# Master-MCU.net
KiCad netlist of a schematic drawn in Altium Designer
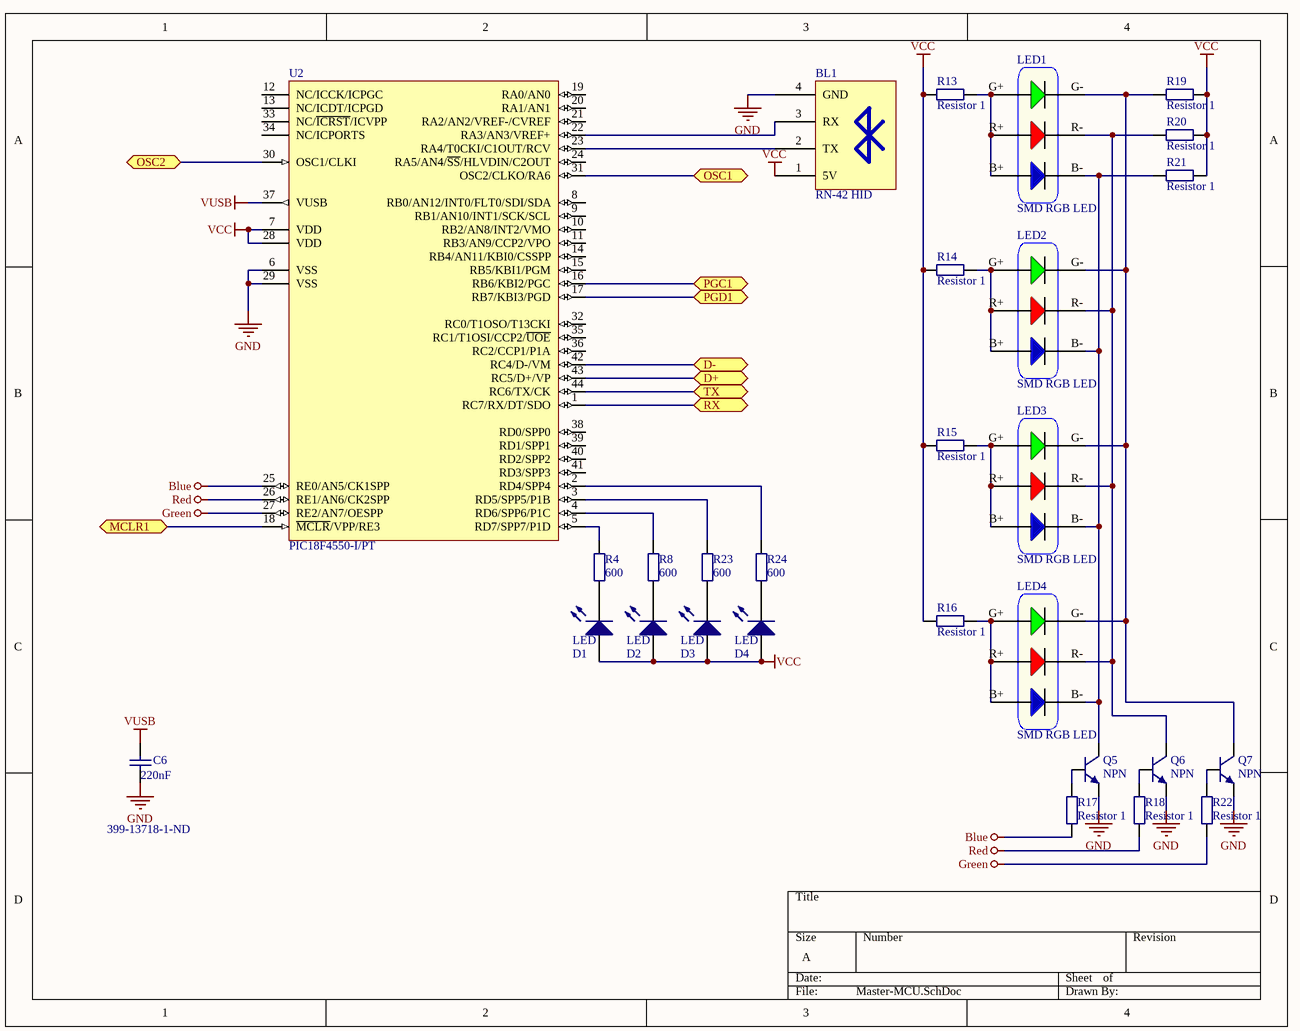
[diagram p0: Master-MCU.SchDoc]

(export (version "E")
  (design (tool "Eeschema 10.0.6"))
  (components
    (comp (ref "BL1")
      (value "RN-42 HID")
      (footprint "Bluetooth module for PCB mounting")
      (libsource (lib "RN42 Breakout SCH Library") (part "Bluetooth module for PCB mounting"))
    )
    (comp (ref "C6")
      (value "220nF")
      (footprint "C-0603")
      (description "Capacitor")
      (fields (field (name "SUPPLIER PART NUMBER 1") "399-13718-1-ND"))
      (libsource (lib "Max Library") (part "Capacitor 1"))
    )
    (comp (ref "D1")
      (value "LED")
      (footprint "JV Footprints:LED-SMD-R")
      (description "Typical LED")
      (fields (field (name "PUBLISHER") "Altium Limited"))
      (libsource (lib "Max Library") (part "LED"))
    )
    (comp (ref "D2")
      (value "LED")
      (footprint "JV Footprints:LED-SMD-R")
      (description "Typical LED")
      (fields (field (name "PUBLISHER") "Altium Limited"))
      (libsource (lib "Max Library") (part "LED"))
    )
    (comp (ref "D3")
      (value "LED")
      (footprint "LED-SMD-R")
      (description "Typical LED")
      (fields (field (name "PUBLISHER") "Altium Limited"))
      (libsource (lib "Max Library") (part "LED"))
    )
    (comp (ref "D4")
      (value "LED")
      (footprint "LED-SMD-R")
      (description "Typical LED")
      (fields (field (name "PUBLISHER") "Altium Limited"))
      (libsource (lib "Max Library") (part "LED"))
    )
    (comp (ref "LED1")
      (value "SMD RGB LED")
      (footprint "SMD LED")
      (description "https://www.tweaking4all.com/wp-content/uploads/2014/01/5050LED.pdf")
      (libsource (lib "LED SYMBOL") (part "LED"))
    )
    (comp (ref "LED2")
      (value "SMD RGB LED")
      (footprint "SMD LED")
      (description "https://www.tweaking4all.com/wp-content/uploads/2014/01/5050LED.pdf")
      (libsource (lib "LED SYMBOL") (part "LED"))
    )
    (comp (ref "LED3")
      (value "SMD RGB LED")
      (footprint "SMD LED")
      (description "https://www.tweaking4all.com/wp-content/uploads/2014/01/5050LED.pdf")
      (libsource (lib "LED SYMBOL") (part "LED"))
    )
    (comp (ref "LED4")
      (value "SMD RGB LED")
      (footprint "SMD LED")
      (description "https://www.tweaking4all.com/wp-content/uploads/2014/01/5050LED.pdf")
      (libsource (lib "LED SYMBOL") (part "LED"))
    )
    (comp (ref "Q5")
      (value "NPN")
      (footprint "JV Footprints:SOT95P237X111-3M-JV")
      (description "NPN General Purpose Amplifier")
      (fields (field (name "PUBLISHER") "Altium Limited"))
      (libsource (lib "Max Library") (part "Transistor NPN"))
    )
    (comp (ref "Q6")
      (value "NPN")
      (footprint "JV Footprints:SOT95P237X111-3M-JV")
      (description "NPN General Purpose Amplifier")
      (fields (field (name "PUBLISHER") "Altium Limited"))
      (libsource (lib "Max Library") (part "Transistor NPN"))
    )
    (comp (ref "Q7")
      (value "NPN")
      (footprint "JV Footprints:SOT95P237X111-3M-JV")
      (description "NPN General Purpose Amplifier")
      (fields (field (name "PUBLISHER") "Altium Limited"))
      (libsource (lib "Max Library") (part "Transistor NPN"))
    )
    (comp (ref "R4")
      (value "600")
      (footprint "JV Footprints:R-0603-3D")
      (description "Resistor")
      (libsource (lib "Max Library") (part "Resistor 1"))
    )
    (comp (ref "R8")
      (value "600")
      (footprint "JV Footprints:R-0603-3D")
      (description "Resistor")
      (libsource (lib "Max Library") (part "Resistor 1"))
    )
    (comp (ref "R13")
      (value "Resistor 1")
      (footprint "JV Footprints:R-0603-3D")
      (description "Resistor")
      (libsource (lib "") (part "Resistor 1_2"))
    )
    (comp (ref "R14")
      (value "Resistor 1")
      (footprint "JV Footprints:R-0603-3D")
      (description "Resistor")
      (libsource (lib "") (part "Resistor 1_2"))
    )
    (comp (ref "R15")
      (value "Resistor 1")
      (footprint "JV Footprints:R-0603-3D")
      (description "Resistor")
      (libsource (lib "") (part "Resistor 1_2"))
    )
    (comp (ref "R16")
      (value "Resistor 1")
      (footprint "JV Footprints:R-0603-3D")
      (description "Resistor")
      (libsource (lib "") (part "Resistor 1_2"))
    )
    (comp (ref "R17")
      (value "Resistor 1")
      (footprint "JV Footprints:R-0603-3D")
      (description "Resistor")
      (libsource (lib "") (part "Resistor 1_3"))
    )
    (comp (ref "R18")
      (value "Resistor 1")
      (footprint "JV Footprints:R-0603-3D")
      (description "Resistor")
      (libsource (lib "") (part "Resistor 1_3"))
    )
    (comp (ref "R19")
      (value "Resistor 1")
      (footprint "R-0603-3D")
      (description "Resistor")
      (libsource (lib "") (part "Resistor 1_1"))
    )
    (comp (ref "R20")
      (value "Resistor 1")
      (footprint "JV Footprints:R-0603-3D")
      (description "Resistor")
      (libsource (lib "") (part "Resistor 1_1"))
    )
    (comp (ref "R21")
      (value "Resistor 1")
      (footprint "JV Footprints:R-0603-3D")
      (description "Resistor")
      (libsource (lib "") (part "Resistor 1_1"))
    )
    (comp (ref "R22")
      (value "Resistor 1")
      (footprint "JV Footprints:R-0603-3D")
      (description "Resistor")
      (libsource (lib "") (part "Resistor 1_3"))
    )
    (comp (ref "R23")
      (value "600")
      (footprint "JV Footprints:R-0603-3D")
      (description "Resistor")
      (libsource (lib "Max Library") (part "Resistor 1"))
    )
    (comp (ref "R24")
      (value "600")
      (footprint "JV Footprints:R-0603-3D")
      (description "Resistor")
      (libsource (lib "Max Library") (part "Resistor 1"))
    )
    (comp (ref "U2")
      (value "PIC18F4550-I/PT")
      (footprint "JV Footprints:TQFP-44_JV")
      (fields (field (name "PUBLISHER") "Altium Limited"))
      (libsource (lib "Microchip Microcontroller 8-Bit PIC18") (part "PIC18F4550-I/PT"))
    )
  )
  (nets
    (net (code "1") (name "/D+") (class "Default")
      (node (ref "U2") (pin "43") (pinfunction "RC5/D+/VP_43") (pintype "bidirectional"))
    )
    (net (code "2") (name "/D-") (class "Default")
      (node (ref "U2") (pin "42") (pinfunction "RC4/D-/VM_42") (pintype "bidirectional"))
    )
    (net (code "3") (name "/MCLR1") (class "Default")
      (node (ref "U2") (pin "18") (pinfunction "~{MCLR}/VPP/RE3_18") (pintype "input"))
    )
    (net (code "4") (name "/OSC1") (class "Default")
      (node (ref "U2") (pin "31") (pinfunction "OSC2/CLKO/RA6_31") (pintype "bidirectional"))
    )
    (net (code "5") (name "/OSC2") (class "Default")
      (node (ref "U2") (pin "30") (pinfunction "OSC1/CLKI_30") (pintype "input"))
    )
    (net (code "6") (name "/PGC1") (class "Default")
      (node (ref "U2") (pin "16") (pinfunction "RB6/KBI2/PGC_16") (pintype "bidirectional"))
    )
    (net (code "7") (name "/PGD1") (class "Default")
      (node (ref "U2") (pin "17") (pinfunction "RB7/KBI3/PGD_17") (pintype "bidirectional"))
    )
    (net (code "8") (name "/RX") (class "Default")
      (node (ref "U2") (pin "1") (pinfunction "RC7/RX/DT/SDO_1") (pintype "bidirectional"))
    )
    (net (code "9") (name "/TX") (class "Default")
      (node (ref "U2") (pin "44") (pinfunction "RC6/TX/CK_44") (pintype "bidirectional"))
    )
    (net (code "10") (name "Blue") (class "Default")
      (node (ref "R17") (pin "1") (pinfunction "1_1") (pintype "passive"))
      (node (ref "U2") (pin "25") (pinfunction "RE0/AN5/CK1SPP_25") (pintype "bidirectional"))
    )
    (net (code "11") (name "GND") (class "Default")
      (node (ref "BL1") (pin "4") (pinfunction "GND_4") (pintype "power_in"))
      (node (ref "C6") (pin "1") (pinfunction "1_1") (pintype "passive"))
      (node (ref "Q5") (pin "1") (pinfunction "E_1") (pintype "passive"))
      (node (ref "Q6") (pin "1") (pinfunction "E_1") (pintype "passive"))
      (node (ref "Q7") (pin "1") (pinfunction "E_1") (pintype "passive"))
      (node (ref "U2") (pin "29") (pinfunction "VSS_29") (pintype "power_in"))
      (node (ref "U2") (pin "6") (pinfunction "VSS_6") (pintype "power_in"))
    )
    (net (code "12") (name "Green") (class "Default")
      (node (ref "R22") (pin "1") (pinfunction "1_1") (pintype "passive"))
      (node (ref "U2") (pin "27") (pinfunction "RE2/AN7/OESPP_27") (pintype "bidirectional"))
    )
    (net (code "13") (name "Net-(BL1-RX)") (class "Default")
      (node (ref "BL1") (pin "3") (pinfunction "RX_3") (pintype "passive"))
      (node (ref "U2") (pin "22") (pinfunction "RA3/AN3/VREF+_22") (pintype "bidirectional"))
    )
    (net (code "14") (name "Net-(BL1-TX)") (class "Default")
      (node (ref "BL1") (pin "2") (pinfunction "TX_2") (pintype "passive"))
      (node (ref "U2") (pin "23") (pinfunction "RA4/T0CKI/C1OUT/RCV_23") (pintype "bidirectional"))
    )
    (net (code "15") (name "Net-(D1-K)") (class "Default")
      (node (ref "D1") (pin "2") (pinfunction "K_2") (pintype "passive"))
      (node (ref "R4") (pin "2") (pinfunction "2_2") (pintype "passive"))
    )
    (net (code "16") (name "Net-(D2-K)") (class "Default")
      (node (ref "D2") (pin "2") (pinfunction "K_2") (pintype "passive"))
      (node (ref "R8") (pin "2") (pinfunction "2_2") (pintype "passive"))
    )
    (net (code "17") (name "Net-(D3-K)") (class "Default")
      (node (ref "D3") (pin "2") (pinfunction "K_2") (pintype "passive"))
      (node (ref "R23") (pin "2") (pinfunction "2_2") (pintype "passive"))
    )
    (net (code "18") (name "Net-(D4-K)") (class "Default")
      (node (ref "D4") (pin "2") (pinfunction "K_2") (pintype "passive"))
      (node (ref "R24") (pin "2") (pinfunction "2_2") (pintype "passive"))
    )
    (net (code "19") (name "Net-(LED1-PadB+)") (class "Default")
      (node (ref "LED1") (pin "B+") (pinfunction "B+_B+") (pintype "passive"))
      (node (ref "LED1") (pin "G+") (pinfunction "G+_G+") (pintype "passive"))
      (node (ref "LED1") (pin "R+") (pinfunction "R+_R+") (pintype "passive"))
      (node (ref "R13") (pin "2") (pinfunction "2_2") (pintype "passive"))
    )
    (net (code "20") (name "Net-(LED2-PadB+)") (class "Default")
      (node (ref "LED2") (pin "B+") (pinfunction "B+_B+") (pintype "passive"))
      (node (ref "LED2") (pin "G+") (pinfunction "G+_G+") (pintype "passive"))
      (node (ref "LED2") (pin "R+") (pinfunction "R+_R+") (pintype "passive"))
      (node (ref "R14") (pin "2") (pinfunction "2_2") (pintype "passive"))
    )
    (net (code "21") (name "Net-(LED3-PadB+)") (class "Default")
      (node (ref "LED3") (pin "B+") (pinfunction "B+_B+") (pintype "passive"))
      (node (ref "LED3") (pin "G+") (pinfunction "G+_G+") (pintype "passive"))
      (node (ref "LED3") (pin "R+") (pinfunction "R+_R+") (pintype "passive"))
      (node (ref "R15") (pin "2") (pinfunction "2_2") (pintype "passive"))
    )
    (net (code "22") (name "Net-(LED4-PadB+)") (class "Default")
      (node (ref "LED4") (pin "B+") (pinfunction "B+_B+") (pintype "passive"))
      (node (ref "LED4") (pin "G+") (pinfunction "G+_G+") (pintype "passive"))
      (node (ref "LED4") (pin "R+") (pinfunction "R+_R+") (pintype "passive"))
      (node (ref "R16") (pin "2") (pinfunction "2_2") (pintype "passive"))
    )
    (net (code "23") (name "Net-(Q5-B)") (class "Default")
      (node (ref "Q5") (pin "2") (pinfunction "B_2") (pintype "passive"))
      (node (ref "R17") (pin "2") (pinfunction "2_2") (pintype "passive"))
    )
    (net (code "24") (name "Net-(Q5-C)") (class "Default")
      (node (ref "LED1") (pin "B-") (pinfunction "B-_B-") (pintype "passive"))
      (node (ref "LED2") (pin "B-") (pinfunction "B-_B-") (pintype "passive"))
      (node (ref "LED3") (pin "B-") (pinfunction "B-_B-") (pintype "passive"))
      (node (ref "LED4") (pin "B-") (pinfunction "B-_B-") (pintype "passive"))
      (node (ref "Q5") (pin "3") (pinfunction "C_3") (pintype "passive"))
      (node (ref "R21") (pin "2") (pinfunction "2_2") (pintype "passive"))
    )
    (net (code "25") (name "Net-(Q6-B)") (class "Default")
      (node (ref "Q6") (pin "2") (pinfunction "B_2") (pintype "passive"))
      (node (ref "R18") (pin "2") (pinfunction "2_2") (pintype "passive"))
    )
    (net (code "26") (name "Net-(Q6-C)") (class "Default")
      (node (ref "LED1") (pin "R-") (pinfunction "R-_R-") (pintype "passive"))
      (node (ref "LED2") (pin "R-") (pinfunction "R-_R-") (pintype "passive"))
      (node (ref "LED3") (pin "R-") (pinfunction "R-_R-") (pintype "passive"))
      (node (ref "LED4") (pin "R-") (pinfunction "R-_R-") (pintype "passive"))
      (node (ref "Q6") (pin "3") (pinfunction "C_3") (pintype "passive"))
      (node (ref "R20") (pin "2") (pinfunction "2_2") (pintype "passive"))
    )
    (net (code "27") (name "Net-(Q7-B)") (class "Default")
      (node (ref "Q7") (pin "2") (pinfunction "B_2") (pintype "passive"))
      (node (ref "R22") (pin "2") (pinfunction "2_2") (pintype "passive"))
    )
    (net (code "28") (name "Net-(Q7-C)") (class "Default")
      (node (ref "LED1") (pin "G-") (pinfunction "G-_G-") (pintype "passive"))
      (node (ref "LED2") (pin "G-") (pinfunction "G-_G-") (pintype "passive"))
      (node (ref "LED3") (pin "G-") (pinfunction "G-_G-") (pintype "passive"))
      (node (ref "LED4") (pin "G-") (pinfunction "G-_G-") (pintype "passive"))
      (node (ref "Q7") (pin "3") (pinfunction "C_3") (pintype "passive"))
      (node (ref "R19") (pin "2") (pinfunction "2_2") (pintype "passive"))
    )
    (net (code "29") (name "Net-(U2-RD4{slash}SPP4)") (class "Default")
      (node (ref "R24") (pin "1") (pinfunction "1_1") (pintype "passive"))
      (node (ref "U2") (pin "2") (pinfunction "RD4/SPP4_2") (pintype "bidirectional"))
    )
    (net (code "30") (name "Net-(U2-RD5{slash}SPP5{slash}P1B)") (class "Default")
      (node (ref "R23") (pin "1") (pinfunction "1_1") (pintype "passive"))
      (node (ref "U2") (pin "3") (pinfunction "RD5/SPP5/P1B_3") (pintype "bidirectional"))
    )
    (net (code "31") (name "Net-(U2-RD6{slash}SPP6{slash}P1C)") (class "Default")
      (node (ref "R8") (pin "1") (pinfunction "1_1") (pintype "passive"))
      (node (ref "U2") (pin "4") (pinfunction "RD6/SPP6/P1C_4") (pintype "bidirectional"))
    )
    (net (code "32") (name "Net-(U2-RD7{slash}SPP7{slash}P1D)") (class "Default")
      (node (ref "R4") (pin "1") (pinfunction "1_1") (pintype "passive"))
      (node (ref "U2") (pin "5") (pinfunction "RD7/SPP7/P1D_5") (pintype "bidirectional"))
    )
    (net (code "33") (name "Red") (class "Default")
      (node (ref "R18") (pin "1") (pinfunction "1_1") (pintype "passive"))
      (node (ref "U2") (pin "26") (pinfunction "RE1/AN6/CK2SPP_26") (pintype "bidirectional"))
    )
    (net (code "34") (name "VCC") (class "Default")
      (node (ref "BL1") (pin "1") (pinfunction "5V_1") (pintype "power_in"))
      (node (ref "D1") (pin "1") (pinfunction "A_1") (pintype "passive"))
      (node (ref "D2") (pin "1") (pinfunction "A_1") (pintype "passive"))
      (node (ref "D3") (pin "1") (pinfunction "A_1") (pintype "passive"))
      (node (ref "D4") (pin "1") (pinfunction "A_1") (pintype "passive"))
      (node (ref "R13") (pin "1") (pinfunction "1_1") (pintype "passive"))
      (node (ref "R14") (pin "1") (pinfunction "1_1") (pintype "passive"))
      (node (ref "R15") (pin "1") (pinfunction "1_1") (pintype "passive"))
      (node (ref "R16") (pin "1") (pinfunction "1_1") (pintype "passive"))
      (node (ref "R19") (pin "1") (pinfunction "1_1") (pintype "passive"))
      (node (ref "R20") (pin "1") (pinfunction "1_1") (pintype "passive"))
      (node (ref "R21") (pin "1") (pinfunction "1_1") (pintype "passive"))
      (node (ref "U2") (pin "28") (pinfunction "VDD_28") (pintype "power_in"))
      (node (ref "U2") (pin "7") (pinfunction "VDD_7") (pintype "power_in"))
    )
    (net (code "35") (name "VUSB") (class "Default")
      (node (ref "C6") (pin "2") (pinfunction "2_2") (pintype "passive"))
      (node (ref "U2") (pin "37") (pinfunction "VUSB_37") (pintype "output"))
    )
    (net (code "36") (name "unconnected-(U2-NC{slash}ICCK{slash}ICPGC-Pad12)") (class "Default")
      (node (ref "U2") (pin "12") (pinfunction "NC/ICCK/ICPGC_12") (pintype "passive"))
    )
    (net (code "37") (name "unconnected-(U2-NC{slash}ICDT{slash}ICPGD-Pad13)") (class "Default")
      (node (ref "U2") (pin "13") (pinfunction "NC/ICDT/ICPGD_13") (pintype "passive"))
    )
    (net (code "38") (name "unconnected-(U2-NC{slash}ICPORTS-Pad34)") (class "Default")
      (node (ref "U2") (pin "34") (pinfunction "NC/ICPORTS_34") (pintype "passive"))
    )
    (net (code "39") (name "unconnected-(U2-NC{slash}~{ICRST}{slash}ICVPP-Pad33)") (class "Default")
      (node (ref "U2") (pin "33") (pinfunction "NC/~{ICRST}/ICVPP_33") (pintype "passive"))
    )
    (net (code "40") (name "unconnected-(U2-RA0{slash}AN0-Pad19)") (class "Default")
      (node (ref "U2") (pin "19") (pinfunction "RA0/AN0_19") (pintype "bidirectional"))
    )
    (net (code "41") (name "unconnected-(U2-RA1{slash}AN1-Pad20)") (class "Default")
      (node (ref "U2") (pin "20") (pinfunction "RA1/AN1_20") (pintype "bidirectional"))
    )
    (net (code "42") (name "unconnected-(U2-RA2{slash}AN2{slash}VREF-{slash}CVREF-Pad21)") (class "Default")
      (node (ref "U2") (pin "21") (pinfunction "RA2/AN2/VREF-/CVREF_21") (pintype "bidirectional"))
    )
    (net (code "43") (name "unconnected-(U2-RA5{slash}AN4{slash}~{SS}{slash}HLVDIN{slash}C2OUT-Pad24)") (class "Default")
      (node (ref "U2") (pin "24") (pinfunction "RA5/AN4/~{SS}/HLVDIN/C2OUT_24") (pintype "bidirectional"))
    )
    (net (code "44") (name "unconnected-(U2-RB0{slash}AN12{slash}INT0{slash}FLT0{slash}SDI{slash}SDA-Pad8)") (class "Default")
      (node (ref "U2") (pin "8") (pinfunction "RB0/AN12/INT0/FLT0/SDI/SDA_8") (pintype "bidirectional"))
    )
    (net (code "45") (name "unconnected-(U2-RB1{slash}AN10{slash}INT1{slash}SCK{slash}SCL-Pad9)") (class "Default")
      (node (ref "U2") (pin "9") (pinfunction "RB1/AN10/INT1/SCK/SCL_9") (pintype "bidirectional"))
    )
    (net (code "46") (name "unconnected-(U2-RB2{slash}AN8{slash}INT2{slash}VMO-Pad10)") (class "Default")
      (node (ref "U2") (pin "10") (pinfunction "RB2/AN8/INT2/VMO_10") (pintype "bidirectional"))
    )
    (net (code "47") (name "unconnected-(U2-RB3{slash}AN9{slash}CCP2{slash}VPO-Pad11)") (class "Default")
      (node (ref "U2") (pin "11") (pinfunction "RB3/AN9/CCP2/VPO_11") (pintype "bidirectional"))
    )
    (net (code "48") (name "unconnected-(U2-RB4{slash}AN11{slash}KBI0{slash}CSSPP-Pad14)") (class "Default")
      (node (ref "U2") (pin "14") (pinfunction "RB4/AN11/KBI0/CSSPP_14") (pintype "bidirectional"))
    )
    (net (code "49") (name "unconnected-(U2-RB5{slash}KBI1{slash}PGM-Pad15)") (class "Default")
      (node (ref "U2") (pin "15") (pinfunction "RB5/KBI1/PGM_15") (pintype "bidirectional"))
    )
    (net (code "50") (name "unconnected-(U2-RC0{slash}T1OSO{slash}T13CKI-Pad32)") (class "Default")
      (node (ref "U2") (pin "32") (pinfunction "RC0/T1OSO/T13CKI_32") (pintype "bidirectional"))
    )
    (net (code "51") (name "unconnected-(U2-RC1{slash}T1OSI{slash}CCP2{slash}~{UOE}-Pad35)") (class "Default")
      (node (ref "U2") (pin "35") (pinfunction "RC1/T1OSI/CCP2/~{UOE}_35") (pintype "bidirectional"))
    )
    (net (code "52") (name "unconnected-(U2-RC2{slash}CCP1{slash}P1A-Pad36)") (class "Default")
      (node (ref "U2") (pin "36") (pinfunction "RC2/CCP1/P1A_36") (pintype "bidirectional"))
    )
    (net (code "53") (name "unconnected-(U2-RD0{slash}SPP0-Pad38)") (class "Default")
      (node (ref "U2") (pin "38") (pinfunction "RD0/SPP0_38") (pintype "bidirectional"))
    )
    (net (code "54") (name "unconnected-(U2-RD1{slash}SPP1-Pad39)") (class "Default")
      (node (ref "U2") (pin "39") (pinfunction "RD1/SPP1_39") (pintype "bidirectional"))
    )
    (net (code "55") (name "unconnected-(U2-RD2{slash}SPP2-Pad40)") (class "Default")
      (node (ref "U2") (pin "40") (pinfunction "RD2/SPP2_40") (pintype "bidirectional"))
    )
    (net (code "56") (name "unconnected-(U2-RD3{slash}SPP3-Pad41)") (class "Default")
      (node (ref "U2") (pin "41") (pinfunction "RD3/SPP3_41") (pintype "bidirectional"))
    )
  )
)
